# PK_MUV_L1.net
KiCad netlist of a schematic drawn in EAGLE
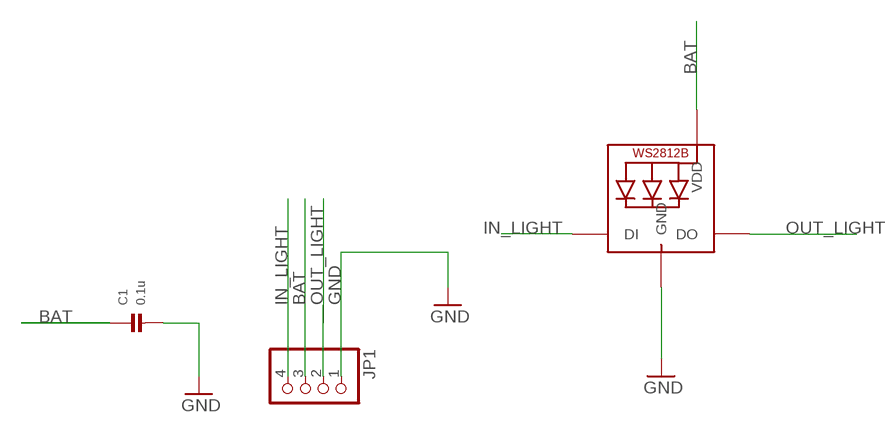
[diagram p0: schematic, sheet 1]

(export (version "E")
  (design (tool "Eeschema 10.0.6"))
  (components
    (comp (ref "C1")
      (value "0.1u")
      (footprint "eagle-import:1206")
      (libsource (lib "eagle-import") (part "CAP_CERAMIC1206"))
    )
    (comp (ref "JP1")
      (value "HEADER-1X4")
      (footprint "eagle-import:1X04_OVAL")
      (libsource (lib "eagle-import") (part "HEADER-1X4"))
    )
    (comp (ref "LED1")
      (value "WS2812B_5050N")
      (footprint "eagle-import:WS2812B-NARROW")
      (libsource (lib "eagle-import") (part "WS2812B_5050N"))
    )
  )
  (nets
    (net (code "1") (name "/BAT") (class "Default")
      (node (ref "C1") (pin "1") (pinfunction "P$1_1") (pintype "passive"))
      (node (ref "JP1") (pin "3") (pinfunction "3_3") (pintype "passive"))
      (node (ref "LED1") (pin "1-VDD") (pinfunction "VDD_1-VDD") (pintype "power_in"))
    )
    (net (code "2") (name "/IN_LIGHT") (class "Default")
      (node (ref "JP1") (pin "4") (pinfunction "4_4") (pintype "passive"))
      (node (ref "LED1") (pin "4-DIN") (pinfunction "DI_4-DIN") (pintype "input"))
    )
    (net (code "3") (name "/OUT_LIGHT") (class "Default")
      (node (ref "JP1") (pin "2") (pinfunction "2_2") (pintype "passive"))
      (node (ref "LED1") (pin "2-DOUT") (pinfunction "DO_2-DOUT") (pintype "output"))
    )
    (net (code "4") (name "GND") (class "Default")
      (node (ref "C1") (pin "2") (pinfunction "P$2_2") (pintype "passive"))
      (node (ref "JP1") (pin "1") (pinfunction "1_1") (pintype "passive"))
      (node (ref "LED1") (pin "3-GND") (pinfunction "GND_3-GND") (pintype "power_in"))
    )
  )
)
